# Buzzer.net
KiCad netlist of a schematic drawn in Altium Designer
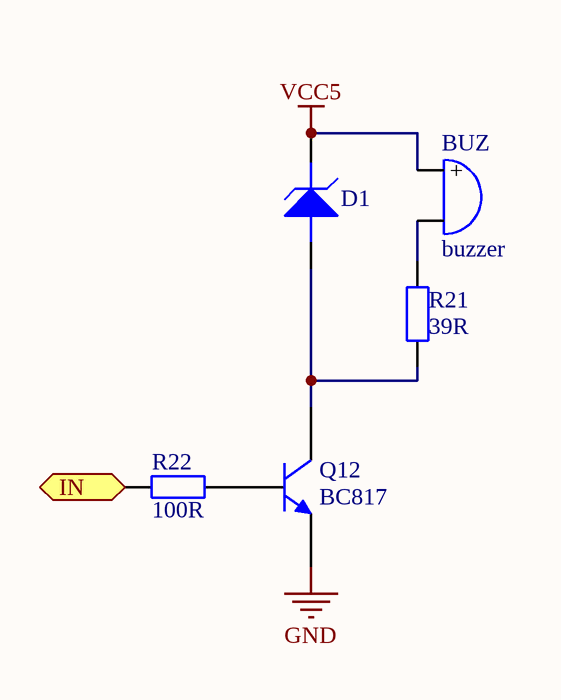
[diagram p0: Buzzer.SchDoc]

(export (version "E")
  (design (tool "Eeschema 10.0.6"))
  (components
    (comp (ref "BUZ") (value "buzzer") (footprint "buzzer") (libsource (lib "iao0w2") (part "buzzer")))
    (comp (ref "D1")
      (value "TRANS SUPPR")
      (footprint "FP_SMA")
      (description "Transient suppressor")
      (fields (field (name "VOLTAGE") "5V"))
      (libsource (lib "hallglib") (part "TRANS SUPPR"))
    )
    (comp (ref "Q12")
      (value "BC817")
      (footprint "FP_SOT23-3")
      (description "NPN Transistor")
      (libsource (lib "hallglib") (part "BC817"))
    )
    (comp (ref "R21")
      (value "39R")
      (footprint "FP_0805_RES")
      (description "Resistor")
      (fields (field (name "TOLERANCE") "5%") (field (name "POWER") "125mW"))
      (libsource (lib "hallglib") (part "RES 39R"))
    )
    (comp (ref "R22")
      (value "100R")
      (footprint "FP_0805_RES")
      (description "Resistor")
      (fields (field (name "TOLERANCE") "5%") (field (name "POWER") "125mW"))
      (libsource (lib "hallglib") (part "RES 100R"))
    )
  )
  (nets
    (net (code "1") (name "/IN") (class "Default")
      (node (ref "R22") (pin "1") (pinfunction "1_1") (pintype "passive"))
    )
    (net (code "2") (name "GND") (class "Default")
      (node (ref "Q12") (pin "1") (pinfunction "E_1") (pintype "passive"))
    )
    (net (code "3") (name "Net-(BUZ--)") (class "Default")
      (node (ref "BUZ") (pin "2") (pinfunction "-_2") (pintype "passive"))
      (node (ref "R21") (pin "2") (pinfunction "2_2") (pintype "passive"))
    )
    (net (code "4") (name "Net-(D1-ANODE)") (class "Default")
      (node (ref "D1") (pin "2") (pinfunction "ANODE_2") (pintype "passive"))
      (node (ref "Q12") (pin "3") (pinfunction "C_3") (pintype "passive"))
      (node (ref "R21") (pin "1") (pinfunction "1_1") (pintype "passive"))
    )
    (net (code "5") (name "Net-(Q12-B)") (class "Default")
      (node (ref "Q12") (pin "2") (pinfunction "B_2") (pintype "passive"))
      (node (ref "R22") (pin "2") (pinfunction "2_2") (pintype "passive"))
    )
    (net (code "6") (name "VCC5") (class "Default")
      (node (ref "BUZ") (pin "1") (pinfunction "+_1") (pintype "passive"))
      (node (ref "D1") (pin "1") (pinfunction "CATHODE_1") (pintype "passive"))
    )
  )
)
